# 1-Schematic_EMW-1_18PIN.net
KiCad netlist of a schematic drawn in EasyEDA
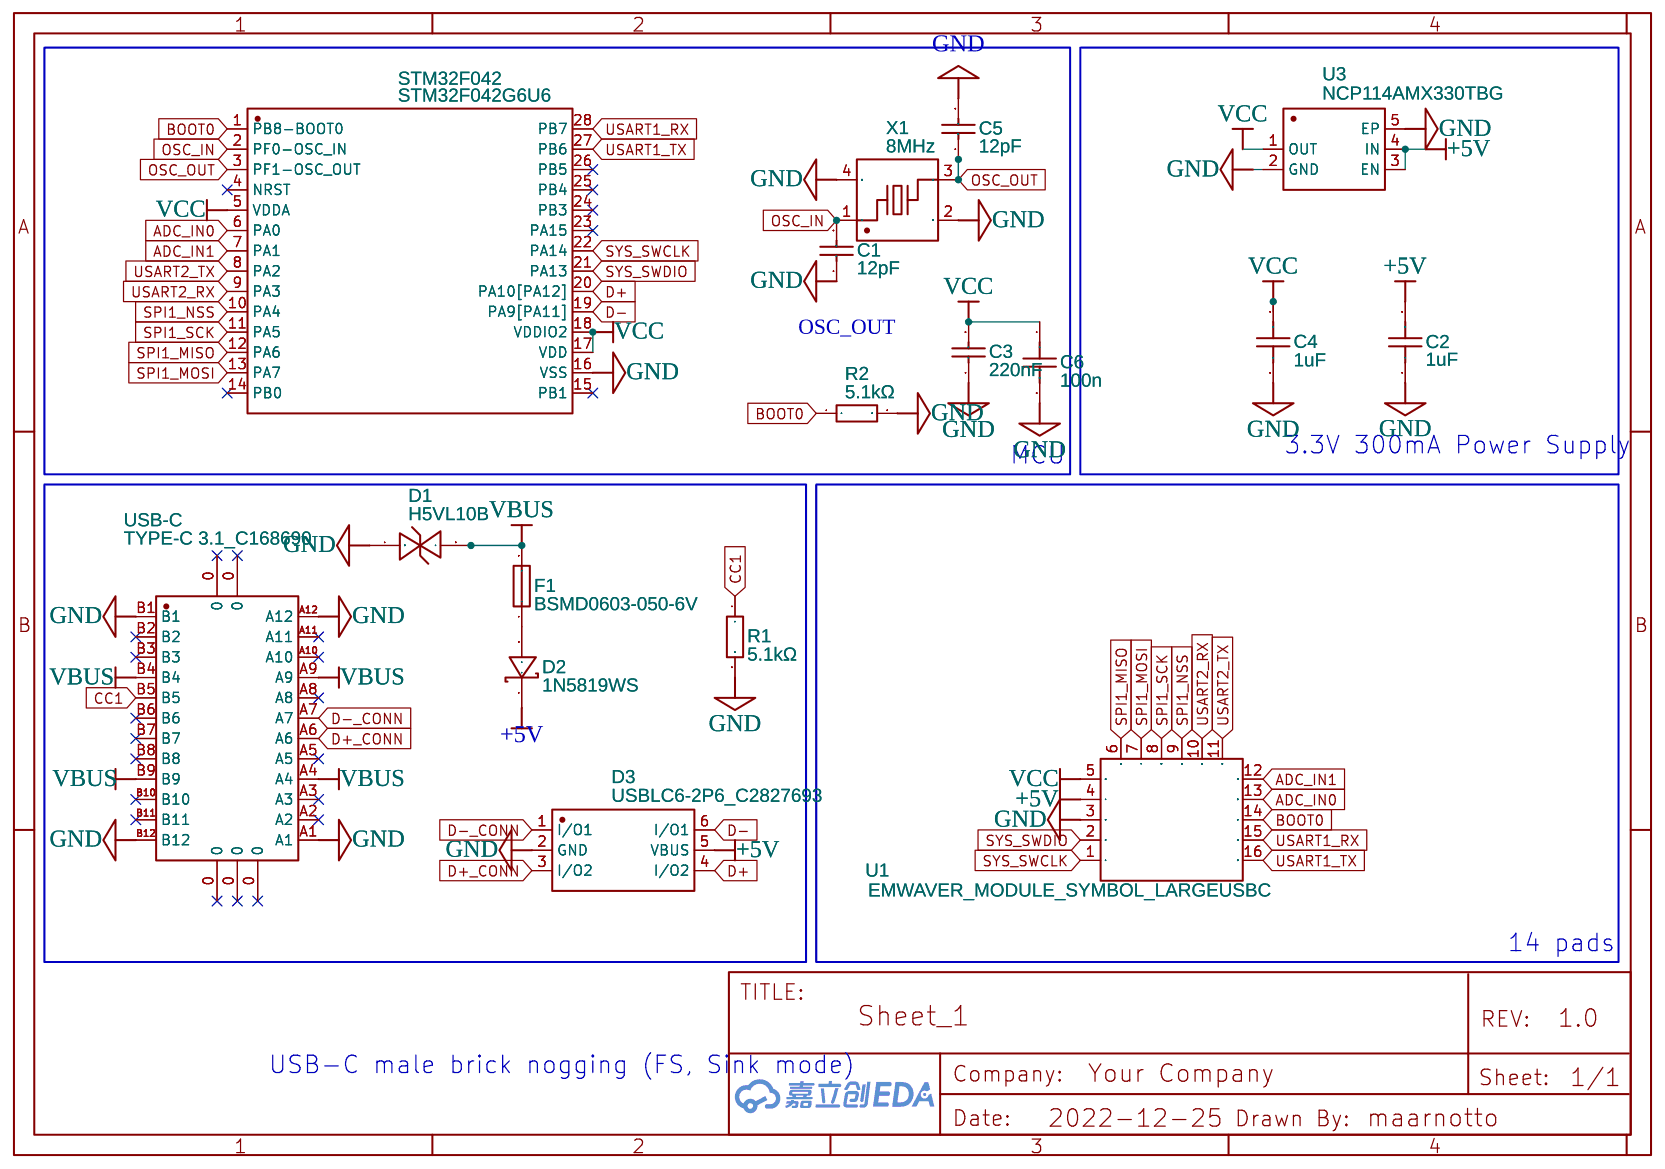
[diagram p0: schematic sheet]

(export (version "E")
  (design (tool "Eeschema 10.0.6"))
  (components
    (comp (ref "C1")
      (value "12pF")
      (fields (field (name "Manufacturer Part") "0402CG120J500NT") (field (name "Manufacturer") "FH(风华)"))
      (libsource (lib "") (part "0402CG120J500NT"))
    )
    (comp (ref "C2") (value "1uF") (libsource (lib "") (part "C_0603_US_1")))
    (comp (ref "C3")
      (value "220nF")
      (fields
        (field (name "Manufacturer Part") "CL05B224KO5NNNC")
        (field (name "Manufacturer") "SAMSUNG(三星)")
      )
      (libsource (lib "") (part "CL05B224KO5NNNC"))
    )
    (comp (ref "C4") (value "1uF") (libsource (lib "") (part "C_0603_US")))
    (comp (ref "C5")
      (value "12pF")
      (fields (field (name "Manufacturer Part") "0402CG120J500NT") (field (name "Manufacturer") "FH(风华)"))
      (libsource (lib "") (part "0402CG120J500NT"))
    )
    (comp (ref "C6") (value "100n") (libsource (lib "") (part "C_0603_US")))
    (comp (ref "D1")
      (value "H5VL10B")
      (fields (field (name "Manufacturer") "宏迦橙"))
      (libsource (lib "") (part "H5VL10B"))
    )
    (comp (ref "D2")
      (value "1N5819WS")
      (fields (field (name "Manufacturer") "Hottech(合科泰)"))
      (libsource (lib "") (part "1N5819WS"))
    )
    (comp (ref "D3")
      (value "USBLC6-2P6_C2827693")
      (fields (field (name "Manufacturer Part") "USBLC6-2P6") (field (name "Manufacturer") "TECH PUBLIC(台舟)"))
      (libsource (lib "") (part "USBLC6-2P6_C2827693"))
    )
    (comp (ref "F1")
      (value "BSMD0603-050-6V")
      (fields (field (name "Manufacturer") "BHFUSE(佰宏)"))
      (libsource (lib "") (part "BSMD0603-050-6V"))
    )
    (comp (ref "R1")
      (value "5.1kΩ")
      (fields
        (field (name "Manufacturer Part") "0402WGF5101TCE")
        (field (name "Manufacturer") "UNI-ROYAL(厚声)")
      )
      (libsource (lib "") (part "0402WGF5101TCE"))
    )
    (comp (ref "R2")
      (value "5.1kΩ")
      (fields
        (field (name "Manufacturer Part") "0402WGF5101TCE")
        (field (name "Manufacturer") "UNI-ROYAL(厚声)")
      )
      (libsource (lib "") (part "0402WGF5101TCE_1"))
    )
    (comp (ref "STM32F042")
      (value "STM32F042G6U6")
      (fields (field (name "Manufacturer") "ST(意法半导体)"))
      (libsource (lib "") (part "STM32F042G6U6"))
    )
    (comp (ref "U1")
      (value "EMWAVER_MODULE_SYMBOL_LARGEUSBC")
      (libsource (lib "") (part "EMWAVER_MODULE_SYMBOL_LARGEUSBC"))
    )
    (comp (ref "U3")
      (value "NCP114AMX330TBG")
      (fields (field (name "Manufacturer") "onsemi(安森美)"))
      (libsource (lib "") (part "NCP114AMX330TBG"))
    )
    (comp (ref "USB-C")
      (value "TYPE-C 3.1_C168690")
      (fields (field (name "Manufacturer Part") "918-118A2021Y40000") (field (name "Manufacturer") "精拓金"))
      (libsource (lib "") (part "TYPE-C 3.1_C168690"))
    )
    (comp (ref "X1")
      (value "8MHz")
      (fields
        (field (name "Manufacturer Part") "XL2EL89COI-111YLC-8M")
        (field (name "Manufacturer") "YXC(扬兴晶振)")
      )
      (libsource (lib "") (part "XL2EL89COI-111YLC-8M"))
    )
  )
  (nets
    (net (code "1") (name "+5V") (class "Default")
      (node (ref "C2") (pin "2") (pinfunction "2_2") (pintype "unspecified"))
      (node (ref "D2") (pin "1") (pinfunction "K_1") (pintype "unspecified"))
      (node (ref "D3") (pin "5") (pinfunction "VBUS_5") (pintype "unspecified"))
      (node (ref "U1") (pin "4") (pinfunction "4_4") (pintype "unspecified"))
      (node (ref "U3") (pin "3") (pinfunction "EN_3") (pintype "unspecified"))
      (node (ref "U3") (pin "4") (pinfunction "IN_4") (pintype "unspecified"))
    )
    (net (code "2") (name "ADC_IN0") (class "Default")
      (node (ref "STM32F042") (pin "6") (pinfunction "PA0_6") (pintype "unspecified"))
      (node (ref "U1") (pin "13") (pinfunction "13_13") (pintype "unspecified"))
    )
    (net (code "3") (name "ADC_IN1") (class "Default")
      (node (ref "STM32F042") (pin "7") (pinfunction "PA1_7") (pintype "unspecified"))
      (node (ref "U1") (pin "12") (pinfunction "12_12") (pintype "unspecified"))
    )
    (net (code "4") (name "BOOT0") (class "Default")
      (node (ref "R2") (pin "1") (pinfunction "1_1") (pintype "input"))
      (node (ref "STM32F042") (pin "1") (pinfunction "PB8-BOOT0_1") (pintype "unspecified"))
      (node (ref "U1") (pin "14") (pinfunction "14_14") (pintype "unspecified"))
    )
    (net (code "5") (name "CC1") (class "Default")
      (node (ref "R1") (pin "1") (pinfunction "1_1") (pintype "input"))
      (node (ref "USB-C") (pin "B5") (pinfunction "B5_B5") (pintype "unspecified"))
    )
    (net (code "6") (name "D+") (class "Default")
      (node (ref "D3") (pin "4") (pinfunction "I/O2_4") (pintype "unspecified"))
      (node (ref "STM32F042") (pin "20") (pinfunction "PA10[PA12]_20") (pintype "unspecified"))
    )
    (net (code "7") (name "D+_CONN") (class "Default")
      (node (ref "D3") (pin "3") (pinfunction "I/O2_3") (pintype "unspecified"))
      (node (ref "USB-C") (pin "A6") (pinfunction "A6_A6") (pintype "unspecified"))
    )
    (net (code "8") (name "D-") (class "Default")
      (node (ref "D3") (pin "6") (pinfunction "I/O1_6") (pintype "unspecified"))
      (node (ref "STM32F042") (pin "19") (pinfunction "PA9[PA11]_19") (pintype "unspecified"))
    )
    (net (code "9") (name "D-_CONN") (class "Default")
      (node (ref "D3") (pin "1") (pinfunction "I/O1_1") (pintype "unspecified"))
      (node (ref "USB-C") (pin "A7") (pinfunction "A7_A7") (pintype "unspecified"))
    )
    (net (code "10") (name "GND") (class "Default")
      (node (ref "C1") (pin "1") (pinfunction "1_1") (pintype "input"))
      (node (ref "C2") (pin "1") (pinfunction "1_1") (pintype "unspecified"))
      (node (ref "C3") (pin "1") (pinfunction "1_1") (pintype "input"))
      (node (ref "C4") (pin "2") (pinfunction "2_2") (pintype "unspecified"))
      (node (ref "C5") (pin "2") (pinfunction "2_2") (pintype "input"))
      (node (ref "C6") (pin "2") (pinfunction "2_2") (pintype "unspecified"))
      (node (ref "D1") (pin "1") (pinfunction "C_1") (pintype "unspecified"))
      (node (ref "D3") (pin "2") (pinfunction "GND_2") (pintype "unspecified"))
      (node (ref "R1") (pin "2") (pinfunction "2_2") (pintype "input"))
      (node (ref "R2") (pin "2") (pinfunction "2_2") (pintype "input"))
      (node (ref "STM32F042") (pin "16") (pinfunction "VSS_16") (pintype "unspecified"))
      (node (ref "U1") (pin "3") (pinfunction "3_3") (pintype "unspecified"))
      (node (ref "U3") (pin "2") (pinfunction "GND_2") (pintype "unspecified"))
      (node (ref "U3") (pin "5") (pinfunction "EP_5") (pintype "unspecified"))
      (node (ref "USB-C") (pin "A1") (pinfunction "A1_A1") (pintype "unspecified"))
      (node (ref "USB-C") (pin "A12") (pinfunction "A12_A12") (pintype "unspecified"))
      (node (ref "USB-C") (pin "B1") (pinfunction "B1_B1") (pintype "unspecified"))
      (node (ref "USB-C") (pin "B12") (pinfunction "B12_B12") (pintype "unspecified"))
      (node (ref "X1") (pin "2") (pinfunction "GND_2") (pintype "input"))
      (node (ref "X1") (pin "4") (pinfunction "GND_4") (pintype "input"))
    )
    (net (code "11") (name "Net-(D2-A)") (class "Default")
      (node (ref "D2") (pin "2") (pinfunction "A_2") (pintype "unspecified"))
      (node (ref "F1") (pin "1") (pinfunction "1_1") (pintype "unspecified"))
    )
    (net (code "12") (name "OSC_IN") (class "Default")
      (node (ref "C1") (pin "2") (pinfunction "2_2") (pintype "input"))
      (node (ref "STM32F042") (pin "2") (pinfunction "PF0-OSC_IN_2") (pintype "unspecified"))
      (node (ref "X1") (pin "1") (pinfunction "1_1") (pintype "input"))
    )
    (net (code "13") (name "OSC_OUT") (class "Default")
      (node (ref "C5") (pin "1") (pinfunction "1_1") (pintype "input"))
      (node (ref "STM32F042") (pin "3") (pinfunction "PF1-OSC_OUT_3") (pintype "unspecified"))
      (node (ref "X1") (pin "3") (pinfunction "3_3") (pintype "input"))
    )
    (net (code "14") (name "SPI1_MISO") (class "Default")
      (node (ref "STM32F042") (pin "12") (pinfunction "PA6_12") (pintype "unspecified"))
      (node (ref "U1") (pin "6") (pinfunction "6_6") (pintype "unspecified"))
    )
    (net (code "15") (name "SPI1_MOSI") (class "Default")
      (node (ref "STM32F042") (pin "13") (pinfunction "PA7_13") (pintype "unspecified"))
      (node (ref "U1") (pin "7") (pinfunction "7_7") (pintype "unspecified"))
    )
    (net (code "16") (name "SPI1_NSS") (class "Default")
      (node (ref "STM32F042") (pin "10") (pinfunction "PA4_10") (pintype "unspecified"))
      (node (ref "U1") (pin "9") (pinfunction "9_9") (pintype "unspecified"))
    )
    (net (code "17") (name "SPI1_SCK") (class "Default")
      (node (ref "STM32F042") (pin "11") (pinfunction "PA5_11") (pintype "unspecified"))
      (node (ref "U1") (pin "8") (pinfunction "8_8") (pintype "unspecified"))
    )
    (net (code "18") (name "SYS_SWCLK") (class "Default")
      (node (ref "STM32F042") (pin "22") (pinfunction "PA14_22") (pintype "unspecified"))
      (node (ref "U1") (pin "1") (pinfunction "1_1") (pintype "unspecified"))
    )
    (net (code "19") (name "SYS_SWDIO") (class "Default")
      (node (ref "STM32F042") (pin "21") (pinfunction "PA13_21") (pintype "unspecified"))
      (node (ref "U1") (pin "2") (pinfunction "2_2") (pintype "unspecified"))
    )
    (net (code "20") (name "USART1_RX") (class "Default")
      (node (ref "STM32F042") (pin "28") (pinfunction "PB7_28") (pintype "unspecified"))
      (node (ref "U1") (pin "15") (pinfunction "15_15") (pintype "unspecified"))
    )
    (net (code "21") (name "USART1_TX") (class "Default")
      (node (ref "STM32F042") (pin "27") (pinfunction "PB6_27") (pintype "unspecified"))
      (node (ref "U1") (pin "16") (pinfunction "16_16") (pintype "unspecified"))
    )
    (net (code "22") (name "USART2_RX") (class "Default")
      (node (ref "STM32F042") (pin "9") (pinfunction "PA3_9") (pintype "unspecified"))
      (node (ref "U1") (pin "10") (pinfunction "10_10") (pintype "unspecified"))
    )
    (net (code "23") (name "USART2_TX") (class "Default")
      (node (ref "STM32F042") (pin "8") (pinfunction "PA2_8") (pintype "unspecified"))
      (node (ref "U1") (pin "11") (pinfunction "11_11") (pintype "unspecified"))
    )
    (net (code "24") (name "VBUS") (class "Default")
      (node (ref "D1") (pin "2") (pinfunction "A_2") (pintype "unspecified"))
      (node (ref "F1") (pin "2") (pinfunction "2_2") (pintype "unspecified"))
      (node (ref "USB-C") (pin "A4") (pinfunction "A4_A4") (pintype "unspecified"))
      (node (ref "USB-C") (pin "A9") (pinfunction "A9_A9") (pintype "unspecified"))
      (node (ref "USB-C") (pin "B4") (pinfunction "B4_B4") (pintype "unspecified"))
      (node (ref "USB-C") (pin "B9") (pinfunction "B9_B9") (pintype "unspecified"))
    )
    (net (code "25") (name "VCC") (class "Default")
      (node (ref "C3") (pin "2") (pinfunction "2_2") (pintype "input"))
      (node (ref "C4") (pin "1") (pinfunction "1_1") (pintype "unspecified"))
      (node (ref "C6") (pin "1") (pinfunction "1_1") (pintype "unspecified"))
      (node (ref "STM32F042") (pin "17") (pinfunction "VDD_17") (pintype "unspecified"))
      (node (ref "STM32F042") (pin "18") (pinfunction "VDDIO2_18") (pintype "unspecified"))
      (node (ref "STM32F042") (pin "5") (pinfunction "VDDA_5") (pintype "unspecified"))
      (node (ref "U1") (pin "5") (pinfunction "5_5") (pintype "unspecified"))
      (node (ref "U3") (pin "1") (pinfunction "OUT_1") (pintype "unspecified"))
    )
    (net (code "26") (name "unconnected-(STM32F042-NRST-Pad4)") (class "Default")
      (node (ref "STM32F042") (pin "4") (pinfunction "NRST_4") (pintype "unspecified+no_connect"))
    )
    (net (code "27") (name "unconnected-(STM32F042-PA15-Pad23)") (class "Default")
      (node (ref "STM32F042") (pin "23") (pinfunction "PA15_23") (pintype "unspecified+no_connect"))
    )
    (net (code "28") (name "unconnected-(STM32F042-PB0-Pad14)") (class "Default")
      (node (ref "STM32F042") (pin "14") (pinfunction "PB0_14") (pintype "unspecified+no_connect"))
    )
    (net (code "29") (name "unconnected-(STM32F042-PB1-Pad15)") (class "Default")
      (node (ref "STM32F042") (pin "15") (pinfunction "PB1_15") (pintype "unspecified+no_connect"))
    )
    (net (code "30") (name "unconnected-(STM32F042-PB3-Pad24)") (class "Default")
      (node (ref "STM32F042") (pin "24") (pinfunction "PB3_24") (pintype "unspecified+no_connect"))
    )
    (net (code "31") (name "unconnected-(STM32F042-PB4-Pad25)") (class "Default")
      (node (ref "STM32F042") (pin "25") (pinfunction "PB4_25") (pintype "unspecified+no_connect"))
    )
    (net (code "32") (name "unconnected-(STM32F042-PB5-Pad26)") (class "Default")
      (node (ref "STM32F042") (pin "26") (pinfunction "PB5_26") (pintype "unspecified+no_connect"))
    )
    (net (code "33") (name "unconnected-(USB-C-Pad0)") (class "Default")
      (node (ref "USB-C") (pin "0") (pinfunction "0_0") (pintype "unspecified+no_connect"))
    )
    (net (code "34") (name "unconnected-(USB-C-Pad0)_1") (class "Default")
      (node (ref "USB-C") (pin "0") (pinfunction "0_0") (pintype "unspecified+no_connect"))
    )
    (net (code "35") (name "unconnected-(USB-C-Pad0)_2") (class "Default")
      (node (ref "USB-C") (pin "0") (pinfunction "0_0") (pintype "unspecified+no_connect"))
    )
    (net (code "36") (name "unconnected-(USB-C-Pad0)_3") (class "Default")
      (node (ref "USB-C") (pin "0") (pinfunction "0_0") (pintype "unspecified+no_connect"))
    )
    (net (code "37") (name "unconnected-(USB-C-Pad0)_4") (class "Default")
      (node (ref "USB-C") (pin "0") (pinfunction "0_0") (pintype "unspecified+no_connect"))
    )
    (net (code "38") (name "unconnected-(USB-C-PadA2)") (class "Default")
      (node (ref "USB-C") (pin "A2") (pinfunction "A2_A2") (pintype "unspecified+no_connect"))
    )
    (net (code "39") (name "unconnected-(USB-C-PadA3)") (class "Default")
      (node (ref "USB-C") (pin "A3") (pinfunction "A3_A3") (pintype "unspecified+no_connect"))
    )
    (net (code "40") (name "unconnected-(USB-C-PadA5)") (class "Default")
      (node (ref "USB-C") (pin "A5") (pinfunction "A5_A5") (pintype "unspecified+no_connect"))
    )
    (net (code "41") (name "unconnected-(USB-C-PadA8)") (class "Default")
      (node (ref "USB-C") (pin "A8") (pinfunction "A8_A8") (pintype "unspecified+no_connect"))
    )
    (net (code "42") (name "unconnected-(USB-C-PadA10)") (class "Default")
      (node (ref "USB-C") (pin "A10") (pinfunction "A10_A10") (pintype "unspecified+no_connect"))
    )
    (net (code "43") (name "unconnected-(USB-C-PadA11)") (class "Default")
      (node (ref "USB-C") (pin "A11") (pinfunction "A11_A11") (pintype "unspecified+no_connect"))
    )
    (net (code "44") (name "unconnected-(USB-C-PadB2)") (class "Default")
      (node (ref "USB-C") (pin "B2") (pinfunction "B2_B2") (pintype "unspecified+no_connect"))
    )
    (net (code "45") (name "unconnected-(USB-C-PadB3)") (class "Default")
      (node (ref "USB-C") (pin "B3") (pinfunction "B3_B3") (pintype "unspecified+no_connect"))
    )
    (net (code "46") (name "unconnected-(USB-C-PadB6)") (class "Default")
      (node (ref "USB-C") (pin "B6") (pinfunction "B6_B6") (pintype "unspecified+no_connect"))
    )
    (net (code "47") (name "unconnected-(USB-C-PadB7)") (class "Default")
      (node (ref "USB-C") (pin "B7") (pinfunction "B7_B7") (pintype "unspecified+no_connect"))
    )
    (net (code "48") (name "unconnected-(USB-C-PadB8)") (class "Default")
      (node (ref "USB-C") (pin "B8") (pinfunction "B8_B8") (pintype "unspecified+no_connect"))
    )
    (net (code "49") (name "unconnected-(USB-C-PadB10)") (class "Default")
      (node (ref "USB-C") (pin "B10") (pinfunction "B10_B10") (pintype "unspecified+no_connect"))
    )
    (net (code "50") (name "unconnected-(USB-C-PadB11)") (class "Default")
      (node (ref "USB-C") (pin "B11") (pinfunction "B11_B11") (pintype "unspecified+no_connect"))
    )
  )
)
